# SparkFun-ESP8266-WiFi-Shield.net
KiCad netlist of a schematic drawn in EAGLE
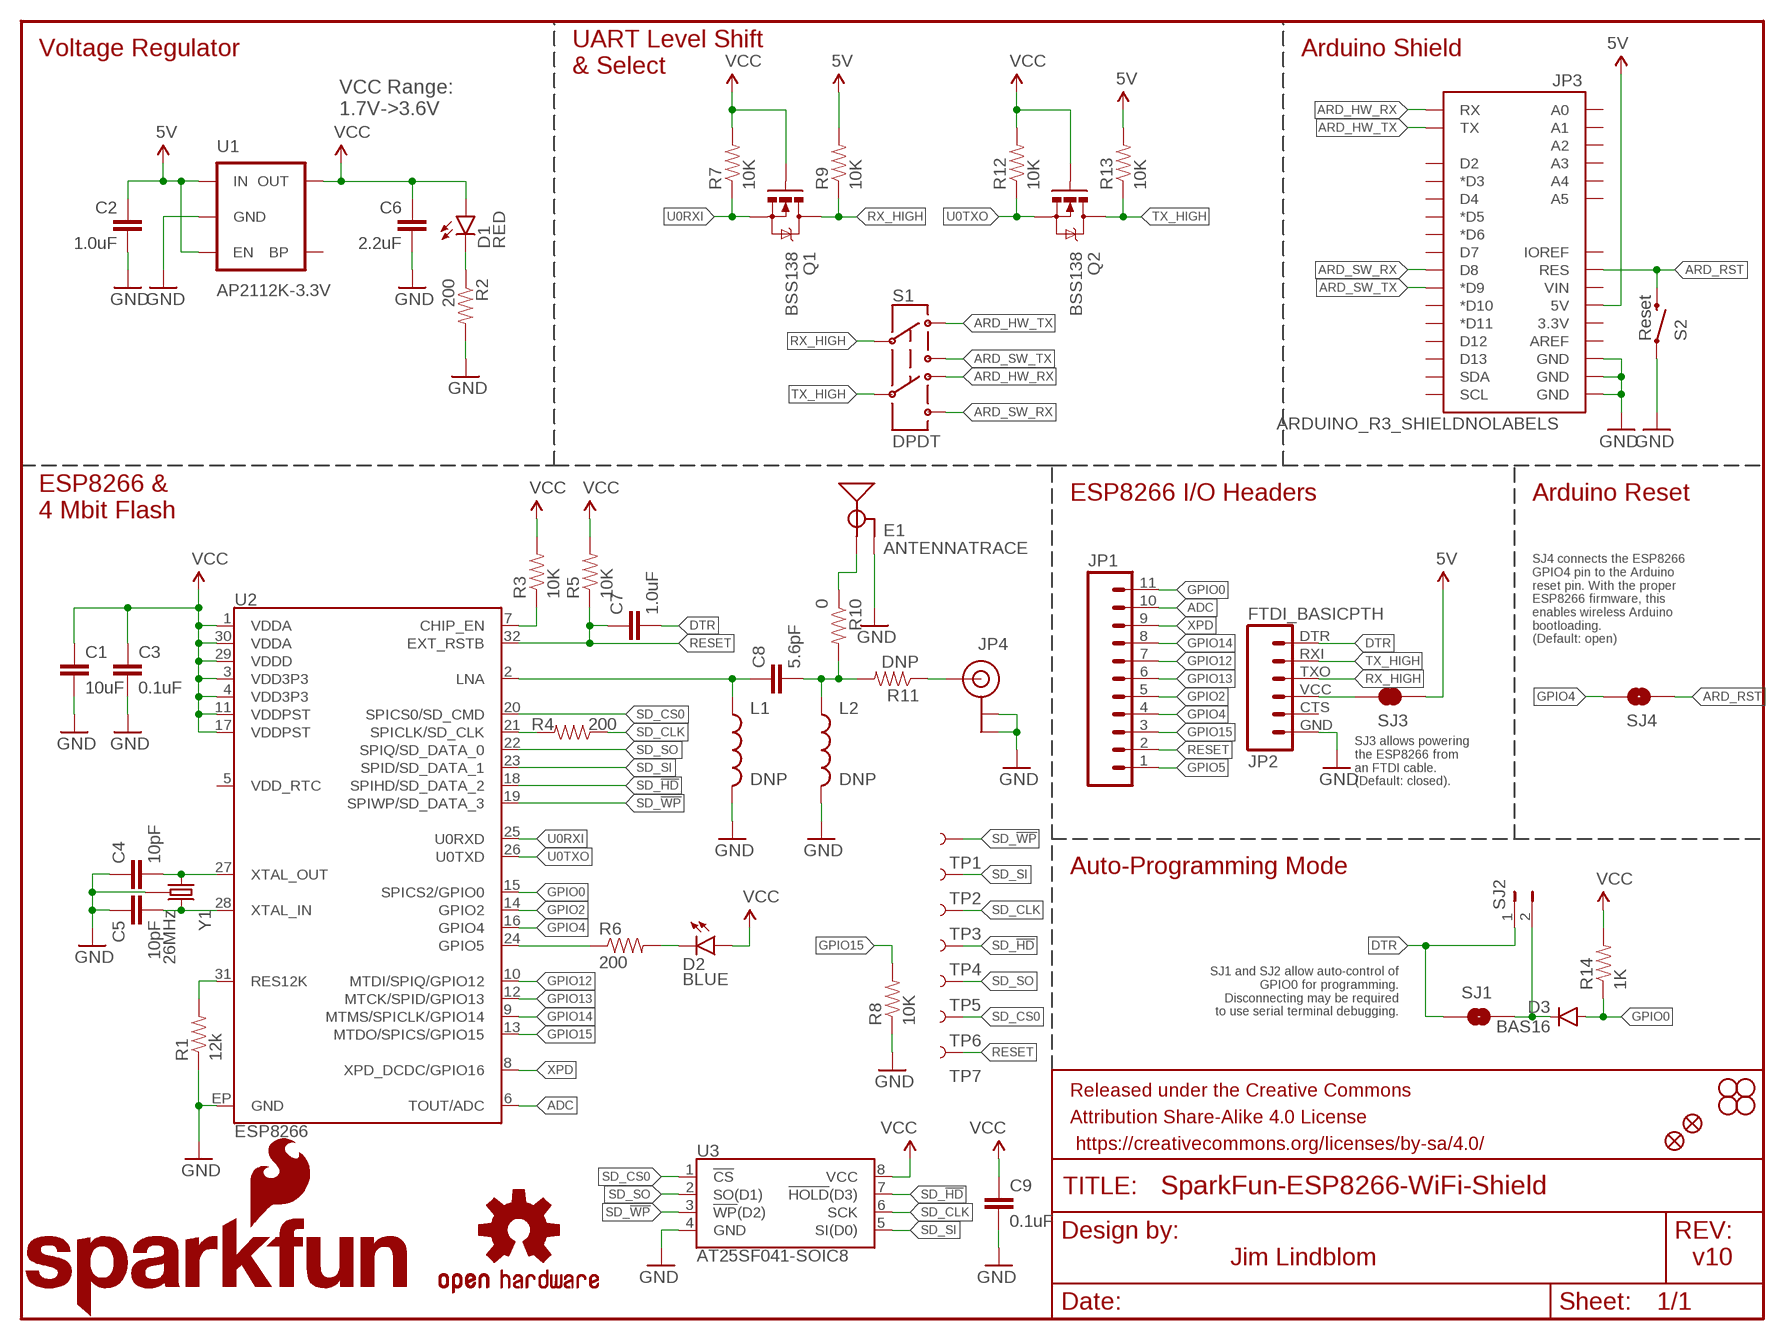
[diagram p0: schematic, sheet 1]

(export (version "E")
  (design (tool "Eeschema 10.0.6"))
  (components
    (comp (ref "C1")
      (value "10uF")
      (footprint "eagle-import:0603-CAP")
      (libsource (lib "eagle-import") (part "10UF-6.3V-20%(0603)"))
    )
    (comp (ref "C2")
      (value "1.0uF")
      (footprint "eagle-import:0805")
      (libsource (lib "eagle-import") (part "1.0UF-25V-+80/-20(0805)"))
    )
    (comp (ref "C3")
      (value "0.1uF")
      (footprint "eagle-import:0603-CAP")
      (libsource (lib "eagle-import") (part "0.1UF-25V(+80/-20%)(0603)"))
    )
    (comp (ref "C4")
      (value "10pF")
      (footprint "eagle-import:0603-CAP")
      (libsource (lib "eagle-import") (part "10PF-50V-5%(0603)"))
    )
    (comp (ref "C5")
      (value "10pF")
      (footprint "eagle-import:0603-CAP")
      (libsource (lib "eagle-import") (part "10PF-50V-5%(0603)"))
    )
    (comp (ref "C6")
      (value "2.2uF")
      (footprint "eagle-import:0603-CAP")
      (libsource (lib "eagle-import") (part "2.2UF-10V-20%(0603)"))
    )
    (comp (ref "C7")
      (value "1.0uF")
      (footprint "eagle-import:0603-CAP")
      (libsource (lib "eagle-import") (part "1.0UF-16V-10%(0603)"))
    )
    (comp (ref "C8")
      (value "5.6pF")
      (footprint "eagle-import:0603-CAP")
      (libsource (lib "eagle-import") (part "CAP0603-CAP"))
    )
    (comp (ref "C9")
      (value "0.1uF")
      (footprint "eagle-import:0603-CAP")
      (libsource (lib "eagle-import") (part "0.1UF-25V(+80/-20%)(0603)"))
    )
    (comp (ref "D1")
      (value "RED")
      (footprint "eagle-import:LED-0603")
      (libsource (lib "eagle-import") (part "LED-RED0603"))
    )
    (comp (ref "D2")
      (value "BLUE")
      (footprint "eagle-import:LED-0603")
      (libsource (lib "eagle-import") (part "LED-BLUE0603"))
    )
    (comp (ref "D3")
      (value "BAS16")
      (footprint "eagle-import:SOD-323")
      (libsource (lib "eagle-import") (part "DIODEBAS16"))
    )
    (comp (ref "E1")
      (value "ANTENNATRACE")
      (footprint "eagle-import:TRACE_ANTENNA_2.4GHZ_25.7MM")
      (libsource (lib "eagle-import") (part "ANTENNATRACE"))
    )
    (comp (ref "FID1")
      (value "FIDUCIAL1X2")
      (footprint "eagle-import:FIDUCIAL-1X2")
      (libsource (lib "eagle-import") (part "FIDUCIAL1X2"))
    )
    (comp (ref "FID2")
      (value "FIDUCIAL1X2")
      (footprint "eagle-import:FIDUCIAL-1X2")
      (libsource (lib "eagle-import") (part "FIDUCIAL1X2"))
    )
    (comp (ref "FRAME1")
      (value "FRAME-LETTER")
      (footprint "eagle-import:CREATIVE_COMMONS")
      (fields (field (name "DESIGNER") "Jim Lindblom"))
      (libsource (lib "eagle-import") (part "FRAME-LETTER"))
    )
    (comp (ref "JP1")
      (value "M11PTH")
      (footprint "eagle-import:1X11")
      (libsource (lib "eagle-import") (part "M11PTH"))
    )
    (comp (ref "JP2")
      (value "FTDI_BASICPTH")
      (footprint "eagle-import:FTDI_BASIC")
      (libsource (lib "eagle-import") (part "FTDI_BASICPTH"))
    )
    (comp (ref "JP3")
      (value "ARDUINO_R3_SHIELDNOLABELS")
      (footprint "eagle-import:UNO_R3_SHIELD_NOLABELS")
      (libsource (lib "eagle-import") (part "ARDUINO_R3_SHIELDNOLABELS"))
    )
    (comp (ref "JP4")
      (value "U.FL")
      (footprint "eagle-import:U.FL")
      (libsource (lib "eagle-import") (part "U.FL"))
    )
    (comp (ref "L1")
      (value "DNP")
      (footprint "eagle-import:0603")
      (libsource (lib "eagle-import") (part "INDUCTOR0603"))
    )
    (comp (ref "L2")
      (value "DNP")
      (footprint "eagle-import:0603")
      (libsource (lib "eagle-import") (part "INDUCTOR0603"))
    )
    (comp (ref "LOGO1")
      (value "SFE_LOGO_NAME_FLAME.2_INCH")
      (footprint "eagle-import:SFE_LOGO_NAME_FLAME_.2")
      (libsource (lib "eagle-import") (part "SFE_LOGO_NAME_FLAME.2_INCH"))
    )
    (comp (ref "LOGO2")
      (value "OSHW-LOGOM")
      (footprint "eagle-import:OSHW-LOGO-M")
      (libsource (lib "eagle-import") (part "OSHW-LOGOM"))
    )
    (comp (ref "Q1")
      (value "BSS138")
      (footprint "eagle-import:SOT23-3")
      (libsource (lib "eagle-import") (part "MOSFET-NCHANNELBSS138"))
    )
    (comp (ref "Q2")
      (value "BSS138")
      (footprint "eagle-import:SOT23-3")
      (libsource (lib "eagle-import") (part "MOSFET-NCHANNELBSS138"))
    )
    (comp (ref "R1")
      (value "12k")
      (footprint "eagle-import:0603-RES")
      (libsource (lib "eagle-import") (part "12KOHM-1/10W-1%(0603)"))
    )
    (comp (ref "R2")
      (value "200")
      (footprint "eagle-import:0603-RES")
      (libsource (lib "eagle-import") (part "200OHM1/10W1%(0603)"))
    )
    (comp (ref "R3")
      (value "10K")
      (footprint "eagle-import:0603-RES")
      (libsource (lib "eagle-import") (part "10KOHM1/10W1%(0603)0603"))
    )
    (comp (ref "R4")
      (value "200")
      (footprint "eagle-import:0603-RES")
      (libsource (lib "eagle-import") (part "200OHM1/10W1%(0603)"))
    )
    (comp (ref "R5")
      (value "10K")
      (footprint "eagle-import:0603-RES")
      (libsource (lib "eagle-import") (part "10KOHM1/10W1%(0603)0603"))
    )
    (comp (ref "R6")
      (value "200")
      (footprint "eagle-import:0603-RES")
      (libsource (lib "eagle-import") (part "200OHM1/10W1%(0603)"))
    )
    (comp (ref "R7")
      (value "10K")
      (footprint "eagle-import:0603-RES")
      (libsource (lib "eagle-import") (part "10KOHM1/10W1%(0603)0603"))
    )
    (comp (ref "R8")
      (value "10K")
      (footprint "eagle-import:0603-RES")
      (libsource (lib "eagle-import") (part "10KOHM1/10W1%(0603)0603"))
    )
    (comp (ref "R9")
      (value "10K")
      (footprint "eagle-import:0603-RES")
      (libsource (lib "eagle-import") (part "10KOHM1/10W1%(0603)0603"))
    )
    (comp (ref "R10")
      (value "0")
      (footprint "eagle-import:0603")
      (libsource (lib "eagle-import") (part "0OHM1/10W5%(0603)"))
    )
    (comp (ref "R11")
      (value "DNP")
      (footprint "eagle-import:0603-RES")
      (libsource (lib "eagle-import") (part "RESISTOR0603-RES"))
    )
    (comp (ref "R12")
      (value "10K")
      (footprint "eagle-import:0603-RES")
      (libsource (lib "eagle-import") (part "10KOHM1/10W1%(0603)0603"))
    )
    (comp (ref "R13")
      (value "10K")
      (footprint "eagle-import:0603-RES")
      (libsource (lib "eagle-import") (part "10KOHM1/10W1%(0603)0603"))
    )
    (comp (ref "R14")
      (value "1K")
      (footprint "eagle-import:0603-RES")
      (libsource (lib "eagle-import") (part "1KOHM1/10W1%(0603)"))
    )
    (comp (ref "S1")
      (value "DPDT")
      (footprint "eagle-import:AYZ0202")
      (libsource (lib "eagle-import") (part "SWITCH-DPDTAYZ0202"))
    )
    (comp (ref "S2")
      (value "Reset")
      (footprint "eagle-import:TACTILE-SWITCH-SMD")
      (libsource (lib "eagle-import") (part "SWITCH-MOMENTARY-2SMD"))
    )
    (comp (ref "SJ1")
      (value "JUMPER-PAD-2-NO")
      (footprint "eagle-import:PAD-JUMPER-2-NO_NO_SILK")
      (libsource (lib "eagle-import") (part "JUMPER-PAD-2-NO"))
    )
    (comp (ref "SJ2")
      (value "JUMPER-PTH-2-NO")
      (footprint "eagle-import:PTH-JUMPER-2-NO_NO_SILK")
      (libsource (lib "eagle-import") (part "JUMPER-PTH-2-NO"))
    )
    (comp (ref "SJ3")
      (value "JUMPER-PAD-2-NC_BY_TRACE")
      (footprint "eagle-import:PAD-JUMPER-2-NC_BY_TRACE_YES_SILK")
      (libsource (lib "eagle-import") (part "JUMPER-PAD-2-NC_BY_TRACE"))
    )
    (comp (ref "SJ4")
      (value "JUMPER-PAD-2-NOYES_SILK")
      (footprint "eagle-import:PAD-JUMPER-2-NO_YES_SILK")
      (libsource (lib "eagle-import") (part "JUMPER-PAD-2-NOYES_SILK"))
    )
    (comp (ref "STANDOFF1")
      (value "STAND-OFF")
      (footprint "eagle-import:STAND-OFF")
      (libsource (lib "eagle-import") (part "STAND-OFF"))
    )
    (comp (ref "STANDOFF2")
      (value "STAND-OFF")
      (footprint "eagle-import:STAND-OFF")
      (libsource (lib "eagle-import") (part "STAND-OFF"))
    )
    (comp (ref "STANDOFF3")
      (value "STAND-OFF")
      (footprint "eagle-import:STAND-OFF")
      (libsource (lib "eagle-import") (part "STAND-OFF"))
    )
    (comp (ref "STANDOFF4")
      (value "STAND-OFF")
      (footprint "eagle-import:STAND-OFF")
      (libsource (lib "eagle-import") (part "STAND-OFF"))
    )
    (comp (ref "TP1")
      (value "TEST-POINT3X5")
      (footprint "eagle-import:PAD.03X.05")
      (libsource (lib "eagle-import") (part "TEST-POINT3X5"))
    )
    (comp (ref "TP2")
      (value "TEST-POINT3X5")
      (footprint "eagle-import:PAD.03X.05")
      (libsource (lib "eagle-import") (part "TEST-POINT3X5"))
    )
    (comp (ref "TP3")
      (value "TEST-POINT3X5")
      (footprint "eagle-import:PAD.03X.05")
      (libsource (lib "eagle-import") (part "TEST-POINT3X5"))
    )
    (comp (ref "TP4")
      (value "TEST-POINT3X5")
      (footprint "eagle-import:PAD.03X.05")
      (libsource (lib "eagle-import") (part "TEST-POINT3X5"))
    )
    (comp (ref "TP5")
      (value "TEST-POINT3X5")
      (footprint "eagle-import:PAD.03X.05")
      (libsource (lib "eagle-import") (part "TEST-POINT3X5"))
    )
    (comp (ref "TP6")
      (value "TEST-POINT3X5")
      (footprint "eagle-import:PAD.03X.05")
      (libsource (lib "eagle-import") (part "TEST-POINT3X5"))
    )
    (comp (ref "TP7")
      (value "TEST-POINT3X5")
      (footprint "eagle-import:PAD.03X.05")
      (libsource (lib "eagle-import") (part "TEST-POINT3X5"))
    )
    (comp (ref "U1")
      (value "AP2112K-3.3V")
      (footprint "eagle-import:SOT23-5")
      (libsource (lib "eagle-import") (part "V_REG_LDOSMD"))
    )
    (comp (ref "U2")
      (value "ESP8266")
      (footprint "eagle-import:QFN32")
      (libsource (lib "eagle-import") (part "ESP8266"))
    )
    (comp (ref "U3")
      (value "AT25SF041-SOIC8")
      (footprint "eagle-import:SO08")
      (libsource (lib "eagle-import") (part "AT25SF041-SOIC8"))
    )
    (comp (ref "Y1")
      (value "26MHz")
      (footprint "eagle-import:CRYSTAL-SMD-3.2X2.5")
      (libsource (lib "eagle-import") (part "CRYSTAL-GROUNDED3.2X2.5"))
    )
  )
  (nets
    (net (code "1") (name "/SD_~{HD}") (class "Default")
      (node (ref "TP4") (pin "P$1") (pinfunction "1_P$1") (pintype "bidirectional"))
      (node (ref "U2") (pin "18") (pinfunction "SPIHD/SD_DATA_2_18") (pintype "bidirectional"))
      (node (ref "U3") (pin "7") (pinfunction "~{HOLD}(D3)_7") (pintype "bidirectional"))
    )
    (net (code "2") (name "/SD_~{WP}") (class "Default")
      (node (ref "TP1") (pin "P$1") (pinfunction "1_P$1") (pintype "bidirectional"))
      (node (ref "U2") (pin "19") (pinfunction "SPIWP/SD_DATA_3_19") (pintype "bidirectional"))
      (node (ref "U3") (pin "3") (pinfunction "~{WP}(D2)_3") (pintype "bidirectional"))
    )
    (net (code "3") (name "5V") (class "Default")
      (node (ref "C2") (pin "1") (pinfunction "1_1") (pintype "passive"))
      (node (ref "JP3") (pin "5V") (pinfunction "5V_5V") (pintype "bidirectional"))
      (node (ref "R13") (pin "2") (pinfunction "2_2") (pintype "passive"))
      (node (ref "R9") (pin "2") (pinfunction "2_2") (pintype "passive"))
      (node (ref "SJ3") (pin "1") (pinfunction "1_1") (pintype "passive"))
      (node (ref "U1") (pin "1") (pinfunction "IN_1") (pintype "input"))
      (node (ref "U1") (pin "3") (pinfunction "EN_3") (pintype "input"))
    )
    (net (code "4") (name "ADC") (class "Default")
      (node (ref "JP1") (pin "10") (pinfunction "10_10") (pintype "passive"))
      (node (ref "U2") (pin "6") (pinfunction "TOUT/ADC_6") (pintype "bidirectional"))
    )
    (net (code "5") (name "ARD_HW_RX") (class "Default")
      (node (ref "JP3") (pin "RX") (pinfunction "RX_RX") (pintype "bidirectional"))
      (node (ref "S1") (pin "4") (pinfunction "4_4") (pintype "bidirectional"))
    )
    (net (code "6") (name "ARD_HW_TX") (class "Default")
      (node (ref "JP3") (pin "TX") (pinfunction "TX_TX") (pintype "bidirectional"))
      (node (ref "S1") (pin "1") (pinfunction "1_1") (pintype "bidirectional"))
    )
    (net (code "7") (name "ARD_RST") (class "Default")
      (node (ref "JP3") (pin "RES") (pinfunction "RES_RES") (pintype "bidirectional"))
      (node (ref "S2") (pin "3") (pinfunction "2_3") (pintype "passive"))
      (node (ref "SJ4") (pin "1") (pinfunction "1_1") (pintype "passive"))
    )
    (net (code "8") (name "ARD_SW_RX") (class "Default")
      (node (ref "JP3") (pin "D8") (pinfunction "D8_D8") (pintype "bidirectional"))
      (node (ref "S1") (pin "6") (pinfunction "6_6") (pintype "bidirectional"))
    )
    (net (code "9") (name "ARD_SW_TX") (class "Default")
      (node (ref "JP3") (pin "D9") (pinfunction "*D9_D9") (pintype "bidirectional"))
      (node (ref "S1") (pin "3") (pinfunction "3_3") (pintype "bidirectional"))
    )
    (net (code "10") (name "DTR") (class "Default")
      (node (ref "C7") (pin "2") (pinfunction "2_2") (pintype "passive"))
      (node (ref "JP2") (pin "DTR") (pinfunction "1_DTR") (pintype "passive"))
      (node (ref "SJ1") (pin "1") (pinfunction "1_1") (pintype "passive"))
      (node (ref "SJ2") (pin "1") (pinfunction "1_1") (pintype "passive"))
    )
    (net (code "11") (name "GND") (class "Default")
      (node (ref "C1") (pin "2") (pinfunction "2_2") (pintype "passive"))
      (node (ref "C2") (pin "2") (pinfunction "2_2") (pintype "passive"))
      (node (ref "C3") (pin "2") (pinfunction "2_2") (pintype "passive"))
      (node (ref "C4") (pin "1") (pinfunction "1_1") (pintype "passive"))
      (node (ref "C5") (pin "1") (pinfunction "1_1") (pintype "passive"))
      (node (ref "C6") (pin "2") (pinfunction "2_2") (pintype "passive"))
      (node (ref "C9") (pin "2") (pinfunction "2_2") (pintype "passive"))
      (node (ref "E1") (pin "GND") (pinfunction "GND_GND") (pintype "bidirectional"))
      (node (ref "E1") (pin "GND2") (pinfunction "GND_GND2") (pintype "bidirectional"))
      (node (ref "JP2") (pin "GND") (pinfunction "6_GND") (pintype "passive"))
      (node (ref "JP3") (pin "GND@0") (pinfunction "GND_GND@0") (pintype "bidirectional"))
      (node (ref "JP3") (pin "GND@1") (pinfunction "GND_GND@1") (pintype "bidirectional"))
      (node (ref "JP3") (pin "GND@2") (pinfunction "GND_GND@2") (pintype "bidirectional"))
      (node (ref "JP4") (pin "P$1") (pinfunction "GND_P$1") (pintype "bidirectional"))
      (node (ref "JP4") (pin "P$2") (pinfunction "GND_P$2") (pintype "bidirectional"))
      (node (ref "L1") (pin "2") (pinfunction "2_2") (pintype "passive"))
      (node (ref "L2") (pin "2") (pinfunction "2_2") (pintype "passive"))
      (node (ref "R1") (pin "1") (pinfunction "1_1") (pintype "passive"))
      (node (ref "R2") (pin "2") (pinfunction "2_2") (pintype "passive"))
      (node (ref "R8") (pin "1") (pinfunction "1_1") (pintype "passive"))
      (node (ref "S2") (pin "1") (pinfunction "1_1") (pintype "passive"))
      (node (ref "U1") (pin "2") (pinfunction "GND_2") (pintype "input"))
      (node (ref "U2") (pin "EP") (pinfunction "GND_EP") (pintype "bidirectional"))
      (node (ref "U3") (pin "4") (pinfunction "GND_4") (pintype "bidirectional"))
      (node (ref "Y1") (pin "2") (pinfunction "GND_2") (pintype "passive"))
      (node (ref "Y1") (pin "4") (pinfunction "GND_4") (pintype "passive"))
    )
    (net (code "12") (name "GPIO0") (class "Default")
      (node (ref "D3") (pin "A") (pinfunction "A_A") (pintype "passive"))
      (node (ref "JP1") (pin "11") (pinfunction "11_11") (pintype "passive"))
      (node (ref "R14") (pin "1") (pinfunction "1_1") (pintype "passive"))
      (node (ref "U2") (pin "15") (pinfunction "SPICS2/GPIO0_15") (pintype "bidirectional"))
    )
    (net (code "13") (name "GPIO2") (class "Default")
      (node (ref "JP1") (pin "5") (pinfunction "5_5") (pintype "passive"))
      (node (ref "U2") (pin "14") (pinfunction "GPIO2_14") (pintype "bidirectional"))
    )
    (net (code "14") (name "GPIO4") (class "Default")
      (node (ref "JP1") (pin "4") (pinfunction "4_4") (pintype "passive"))
      (node (ref "SJ4") (pin "2") (pinfunction "2_2") (pintype "passive"))
      (node (ref "U2") (pin "16") (pinfunction "GPIO4_16") (pintype "bidirectional"))
    )
    (net (code "15") (name "GPIO5") (class "Default")
      (node (ref "JP1") (pin "1") (pinfunction "1_1") (pintype "passive"))
      (node (ref "R6") (pin "1") (pinfunction "1_1") (pintype "passive"))
      (node (ref "U2") (pin "24") (pinfunction "GPIO5_24") (pintype "bidirectional"))
    )
    (net (code "16") (name "GPIO12") (class "Default")
      (node (ref "JP1") (pin "7") (pinfunction "7_7") (pintype "passive"))
      (node (ref "U2") (pin "10") (pinfunction "MTDI/SPIQ/GPIO12_10") (pintype "bidirectional"))
    )
    (net (code "17") (name "GPIO13") (class "Default")
      (node (ref "JP1") (pin "6") (pinfunction "6_6") (pintype "passive"))
      (node (ref "U2") (pin "12") (pinfunction "MTCK/SPID/GPIO13_12") (pintype "bidirectional"))
    )
    (net (code "18") (name "GPIO14") (class "Default")
      (node (ref "JP1") (pin "8") (pinfunction "8_8") (pintype "passive"))
      (node (ref "U2") (pin "9") (pinfunction "MTMS/SPICLK/GPIO14_9") (pintype "bidirectional"))
    )
    (net (code "19") (name "GPIO15") (class "Default")
      (node (ref "JP1") (pin "3") (pinfunction "3_3") (pintype "passive"))
      (node (ref "R8") (pin "2") (pinfunction "2_2") (pintype "passive"))
      (node (ref "U2") (pin "13") (pinfunction "MTDO/SPICS/GPIO15_13") (pintype "bidirectional"))
    )
    (net (code "20") (name "Net-(C8-Pad2)") (class "Default")
      (node (ref "C8") (pin "2") (pinfunction "2_2") (pintype "passive"))
      (node (ref "L2") (pin "1") (pinfunction "1_1") (pintype "passive"))
      (node (ref "R10") (pin "2") (pinfunction "2_2") (pintype "passive"))
      (node (ref "R11") (pin "2") (pinfunction "2_2") (pintype "passive"))
    )
    (net (code "21") (name "Net-(D1-PadC)") (class "Default")
      (node (ref "D1") (pin "C") (pinfunction "C_C") (pintype "passive"))
      (node (ref "R2") (pin "1") (pinfunction "1_1") (pintype "passive"))
    )
    (net (code "22") (name "Net-(D2-PadC)") (class "Default")
      (node (ref "D2") (pin "C") (pinfunction "C_C") (pintype "passive"))
      (node (ref "R6") (pin "2") (pinfunction "2_2") (pintype "passive"))
    )
    (net (code "23") (name "Net-(D3-PadC)") (class "Default")
      (node (ref "D3") (pin "C") (pinfunction "C_C") (pintype "passive"))
      (node (ref "SJ1") (pin "2") (pinfunction "2_2") (pintype "passive"))
      (node (ref "SJ2") (pin "2") (pinfunction "2_2") (pintype "passive"))
    )
    (net (code "24") (name "Net-(E1-SIGNAL)") (class "Default")
      (node (ref "E1") (pin "ANT") (pinfunction "SIGNAL_ANT") (pintype "bidirectional"))
      (node (ref "R10") (pin "1") (pinfunction "1_1") (pintype "passive"))
    )
    (net (code "25") (name "Net-(JP2-4)") (class "Default")
      (node (ref "JP2") (pin "VCC") (pinfunction "4_VCC") (pintype "passive"))
      (node (ref "SJ3") (pin "2") (pinfunction "2_2") (pintype "passive"))
    )
    (net (code "26") (name "Net-(JP4-SIGNAL)") (class "Default")
      (node (ref "JP4") (pin "P$3") (pinfunction "SIGNAL_P$3") (pintype "bidirectional"))
      (node (ref "R11") (pin "1") (pinfunction "1_1") (pintype "passive"))
    )
    (net (code "27") (name "Net-(U2-CHIP_EN)") (class "Default")
      (node (ref "R3") (pin "1") (pinfunction "1_1") (pintype "passive"))
      (node (ref "U2") (pin "7") (pinfunction "CHIP_EN_7") (pintype "bidirectional"))
    )
    (net (code "28") (name "Net-(U2-LNA)") (class "Default")
      (node (ref "C8") (pin "1") (pinfunction "1_1") (pintype "passive"))
      (node (ref "L1") (pin "1") (pinfunction "1_1") (pintype "passive"))
      (node (ref "U2") (pin "2") (pinfunction "LNA_2") (pintype "bidirectional"))
    )
    (net (code "29") (name "Net-(U2-RES12K)") (class "Default")
      (node (ref "R1") (pin "2") (pinfunction "2_2") (pintype "passive"))
      (node (ref "U2") (pin "31") (pinfunction "RES12K_31") (pintype "bidirectional"))
    )
    (net (code "30") (name "Net-(U2-SPICLK{slash}SD_CLK)") (class "Default")
      (node (ref "R4") (pin "2") (pinfunction "2_2") (pintype "passive"))
      (node (ref "U2") (pin "21") (pinfunction "SPICLK/SD_CLK_21") (pintype "bidirectional"))
    )
    (net (code "31") (name "Net-(U2-XTAL_IN)") (class "Default")
      (node (ref "C5") (pin "2") (pinfunction "2_2") (pintype "passive"))
      (node (ref "U2") (pin "28") (pinfunction "XTAL_IN_28") (pintype "bidirectional"))
      (node (ref "Y1") (pin "3") (pinfunction "2_3") (pintype "passive"))
    )
    (net (code "32") (name "Net-(U2-XTAL_OUT)") (class "Default")
      (node (ref "C4") (pin "2") (pinfunction "2_2") (pintype "passive"))
      (node (ref "U2") (pin "27") (pinfunction "XTAL_OUT_27") (pintype "bidirectional"))
      (node (ref "Y1") (pin "1") (pinfunction "1_1") (pintype "passive"))
    )
    (net (code "33") (name "RESET") (class "Default")
      (node (ref "C7") (pin "1") (pinfunction "1_1") (pintype "passive"))
      (node (ref "JP1") (pin "2") (pinfunction "2_2") (pintype "passive"))
      (node (ref "R5") (pin "1") (pinfunction "1_1") (pintype "passive"))
      (node (ref "TP7") (pin "P$1") (pinfunction "1_P$1") (pintype "bidirectional"))
      (node (ref "U2") (pin "32") (pinfunction "EXT_RSTB_32") (pintype "bidirectional"))
    )
    (net (code "34") (name "RX_HIGH") (class "Default")
      (node (ref "JP2") (pin "TXO") (pinfunction "3_TXO") (pintype "passive"))
      (node (ref "Q1") (pin "3") (pinfunction "D_3") (pintype "passive"))
      (node (ref "R9") (pin "1") (pinfunction "1_1") (pintype "passive"))
      (node (ref "S1") (pin "2") (pinfunction "2_2") (pintype "bidirectional"))
    )
    (net (code "35") (name "SD_CLK") (class "Default")
      (node (ref "R4") (pin "1") (pinfunction "1_1") (pintype "passive"))
      (node (ref "TP3") (pin "P$1") (pinfunction "1_P$1") (pintype "bidirectional"))
      (node (ref "U3") (pin "6") (pinfunction "SCK_6") (pintype "bidirectional"))
    )
    (net (code "36") (name "SD_CS0") (class "Default")
      (node (ref "TP6") (pin "P$1") (pinfunction "1_P$1") (pintype "bidirectional"))
      (node (ref "U2") (pin "20") (pinfunction "SPICS0/SD_CMD_20") (pintype "bidirectional"))
      (node (ref "U3") (pin "1") (pinfunction "~{CS}_1") (pintype "bidirectional"))
    )
    (net (code "37") (name "SD_SI") (class "Default")
      (node (ref "TP2") (pin "P$1") (pinfunction "1_P$1") (pintype "bidirectional"))
      (node (ref "U2") (pin "23") (pinfunction "SPID/SD_DATA_1_23") (pintype "bidirectional"))
      (node (ref "U3") (pin "5") (pinfunction "SI(D0)_5") (pintype "bidirectional"))
    )
    (net (code "38") (name "SD_SO") (class "Default")
      (node (ref "TP5") (pin "P$1") (pinfunction "1_P$1") (pintype "bidirectional"))
      (node (ref "U2") (pin "22") (pinfunction "SPIQ/SD_DATA_0_22") (pintype "bidirectional"))
      (node (ref "U3") (pin "2") (pinfunction "SO(D1)_2") (pintype "bidirectional"))
    )
    (net (code "39") (name "TX_HIGH") (class "Default")
      (node (ref "JP2") (pin "RXI") (pinfunction "2_RXI") (pintype "passive"))
      (node (ref "Q2") (pin "3") (pinfunction "D_3") (pintype "passive"))
      (node (ref "R13") (pin "1") (pinfunction "1_1") (pintype "passive"))
      (node (ref "S1") (pin "5") (pinfunction "5_5") (pintype "bidirectional"))
    )
    (net (code "40") (name "U0RXI") (class "Default")
      (node (ref "Q1") (pin "2") (pinfunction "S_2") (pintype "passive"))
      (node (ref "R7") (pin "1") (pinfunction "1_1") (pintype "passive"))
      (node (ref "U2") (pin "25") (pinfunction "U0RXD_25") (pintype "bidirectional"))
    )
    (net (code "41") (name "U0TXO") (class "Default")
      (node (ref "Q2") (pin "2") (pinfunction "S_2") (pintype "passive"))
      (node (ref "R12") (pin "1") (pinfunction "1_1") (pintype "passive"))
      (node (ref "U2") (pin "26") (pinfunction "U0TXD_26") (pintype "bidirectional"))
    )
    (net (code "42") (name "VCC") (class "Default")
      (node (ref "C1") (pin "1") (pinfunction "1_1") (pintype "passive"))
      (node (ref "C3") (pin "1") (pinfunction "1_1") (pintype "passive"))
      (node (ref "C6") (pin "1") (pinfunction "1_1") (pintype "passive"))
      (node (ref "C9") (pin "1") (pinfunction "1_1") (pintype "passive"))
      (node (ref "D1") (pin "A") (pinfunction "A_A") (pintype "passive"))
      (node (ref "D2") (pin "A") (pinfunction "A_A") (pintype "passive"))
      (node (ref "Q1") (pin "1") (pinfunction "G_1") (pintype "passive"))
      (node (ref "Q2") (pin "1") (pinfunction "G_1") (pintype "passive"))
      (node (ref "R12") (pin "2") (pinfunction "2_2") (pintype "passive"))
      (node (ref "R14") (pin "2") (pinfunction "2_2") (pintype "passive"))
      (node (ref "R3") (pin "2") (pinfunction "2_2") (pintype "passive"))
      (node (ref "R5") (pin "2") (pinfunction "2_2") (pintype "passive"))
      (node (ref "R7") (pin "2") (pinfunction "2_2") (pintype "passive"))
      (node (ref "U1") (pin "5") (pinfunction "OUT_5") (pintype "passive"))
      (node (ref "U2") (pin "1") (pinfunction "VDDA_1") (pintype "bidirectional"))
      (node (ref "U2") (pin "11") (pinfunction "VDDPST_11") (pintype "bidirectional"))
      (node (ref "U2") (pin "17") (pinfunction "VDDPST_17") (pintype "bidirectional"))
      (node (ref "U2") (pin "29") (pinfunction "VDDD_29") (pintype "bidirectional"))
      (node (ref "U2") (pin "3") (pinfunction "VDD3P3_3") (pintype "bidirectional"))
      (node (ref "U2") (pin "30") (pinfunction "VDDA_30") (pintype "bidirectional"))
      (node (ref "U2") (pin "4") (pinfunction "VDD3P3_4") (pintype "bidirectional"))
      (node (ref "U3") (pin "8") (pinfunction "VCC_8") (pintype "bidirectional"))
    )
    (net (code "43") (name "XPD") (class "Default")
      (node (ref "JP1") (pin "9") (pinfunction "9_9") (pintype "passive"))
      (node (ref "U2") (pin "8") (pinfunction "XPD_DCDC/GPIO16_8") (pintype "bidirectional"))
    )
    (net (code "44") (name "unconnected-(JP2-5-PadCTS)") (class "Default")
      (node (ref "JP2") (pin "CTS") (pinfunction "5_CTS") (pintype "passive"))
    )
    (net (code "45") (name "unconnected-(JP3-*D3-PadD3)") (class "Default")
      (node (ref "JP3") (pin "D3") (pinfunction "*D3_D3") (pintype "bidirectional"))
    )
    (net (code "46") (name "unconnected-(JP3-*D5-PadD5)") (class "Default")
      (node (ref "JP3") (pin "D5") (pinfunction "*D5_D5") (pintype "bidirectional"))
    )
    (net (code "47") (name "unconnected-(JP3-*D6-PadD6)") (class "Default")
      (node (ref "JP3") (pin "D6") (pinfunction "*D6_D6") (pintype "bidirectional"))
    )
    (net (code "48") (name "unconnected-(JP3-*D10-PadD10)") (class "Default")
      (node (ref "JP3") (pin "D10") (pinfunction "*D10_D10") (pintype "bidirectional"))
    )
    (net (code "49") (name "unconnected-(JP3-*D11-PadD11)") (class "Default")
      (node (ref "JP3") (pin "D11") (pinfunction "*D11_D11") (pintype "bidirectional"))
    )
    (net (code "50") (name "unconnected-(JP3-Pad3.3V)") (class "Default")
      (node (ref "JP3") (pin "3.3V") (pinfunction "3.3V_3.3V") (pintype "bidirectional"))
    )
    (net (code "51") (name "unconnected-(JP3-PadA0)") (class "Default")
      (node (ref "JP3") (pin "A0") (pinfunction "A0_A0") (pintype "bidirectional"))
    )
    (net (code "52") (name "unconnected-(JP3-PadA1)") (class "Default")
      (node (ref "JP3") (pin "A1") (pinfunction "A1_A1") (pintype "bidirectional"))
    )
    (net (code "53") (name "unconnected-(JP3-PadA2)") (class "Default")
      (node (ref "JP3") (pin "A2") (pinfunction "A2_A2") (pintype "bidirectional"))
    )
    (net (code "54") (name "unconnected-(JP3-PadA3)") (class "Default")
      (node (ref "JP3") (pin "A3") (pinfunction "A3_A3") (pintype "bidirectional"))
    )
    (net (code "55") (name "unconnected-(JP3-PadA4)") (class "Default")
      (node (ref "JP3") (pin "A4") (pinfunction "A4_A4") (pintype "bidirectional"))
    )
    (net (code "56") (name "unconnected-(JP3-PadA5)") (class "Default")
      (node (ref "JP3") (pin "A5") (pinfunction "A5_A5") (pintype "bidirectional"))
    )
    (net (code "57") (name "unconnected-(JP3-PadAREF)") (class "Default")
      (node (ref "JP3") (pin "AREF") (pinfunction "AREF_AREF") (pintype "bidirectional"))
    )
    (net (code "58") (name "unconnected-(JP3-PadD2)") (class "Default")
      (node (ref "JP3") (pin "D2") (pinfunction "D2_D2") (pintype "bidirectional"))
    )
    (net (code "59") (name "unconnected-(JP3-PadD4)") (class "Default")
      (node (ref "JP3") (pin "D4") (pinfunction "D4_D4") (pintype "bidirectional"))
    )
    (net (code "60") (name "unconnected-(JP3-PadD7)") (class "Default")
      (node (ref "JP3") (pin "D7") (pinfunction "D7_D7") (pintype "bidirectional"))
    )
    (net (code "61") (name "unconnected-(JP3-PadD12)") (class "Default")
      (node (ref "JP3") (pin "D12") (pinfunction "D12_D12") (pintype "bidirectional"))
    )
    (net (code "62") (name "unconnected-(JP3-PadD13)") (class "Default")
      (node (ref "JP3") (pin "D13") (pinfunction "D13_D13") (pintype "bidirectional"))
    )
    (net (code "63") (name "unconnected-(JP3-PadIOREF)") (class "Default")
      (node (ref "JP3") (pin "IOREF") (pinfunction "IOREF_IOREF") (pintype "bidirectional"))
    )
    (net (code "64") (name "unconnected-(JP3-PadSCL)") (class "Default")
      (node (ref "JP3") (pin "SCL") (pinfunction "SCL_SCL") (pintype "bidirectional"))
    )
    (net (code "65") (name "unconnected-(JP3-PadSDA)") (class "Default")
      (node (ref "JP3") (pin "SDA") (pinfunction "SDA_SDA") (pintype "bidirectional"))
    )
    (net (code "66") (name "unconnected-(JP3-PadVIN)") (class "Default")
      (node (ref "JP3") (pin "VIN") (pinfunction "VIN_VIN") (pintype "bidirectional"))
    )
    (net (code "67") (name "unconnected-(U1-BP-Pad4)") (class "Default")
      (node (ref "U1") (pin "4") (pinfunction "BP_4") (pintype "input"))
    )
    (net (code "68") (name "unconnected-(U2-VDD_RTC-Pad5)") (class "Default")
      (node (ref "U2") (pin "5") (pinfunction "VDD_RTC_5") (pintype "bidirectional"))
    )
  )
)
